# bmowdisk.net
KiCad netlist of a schematic drawn in EAGLE
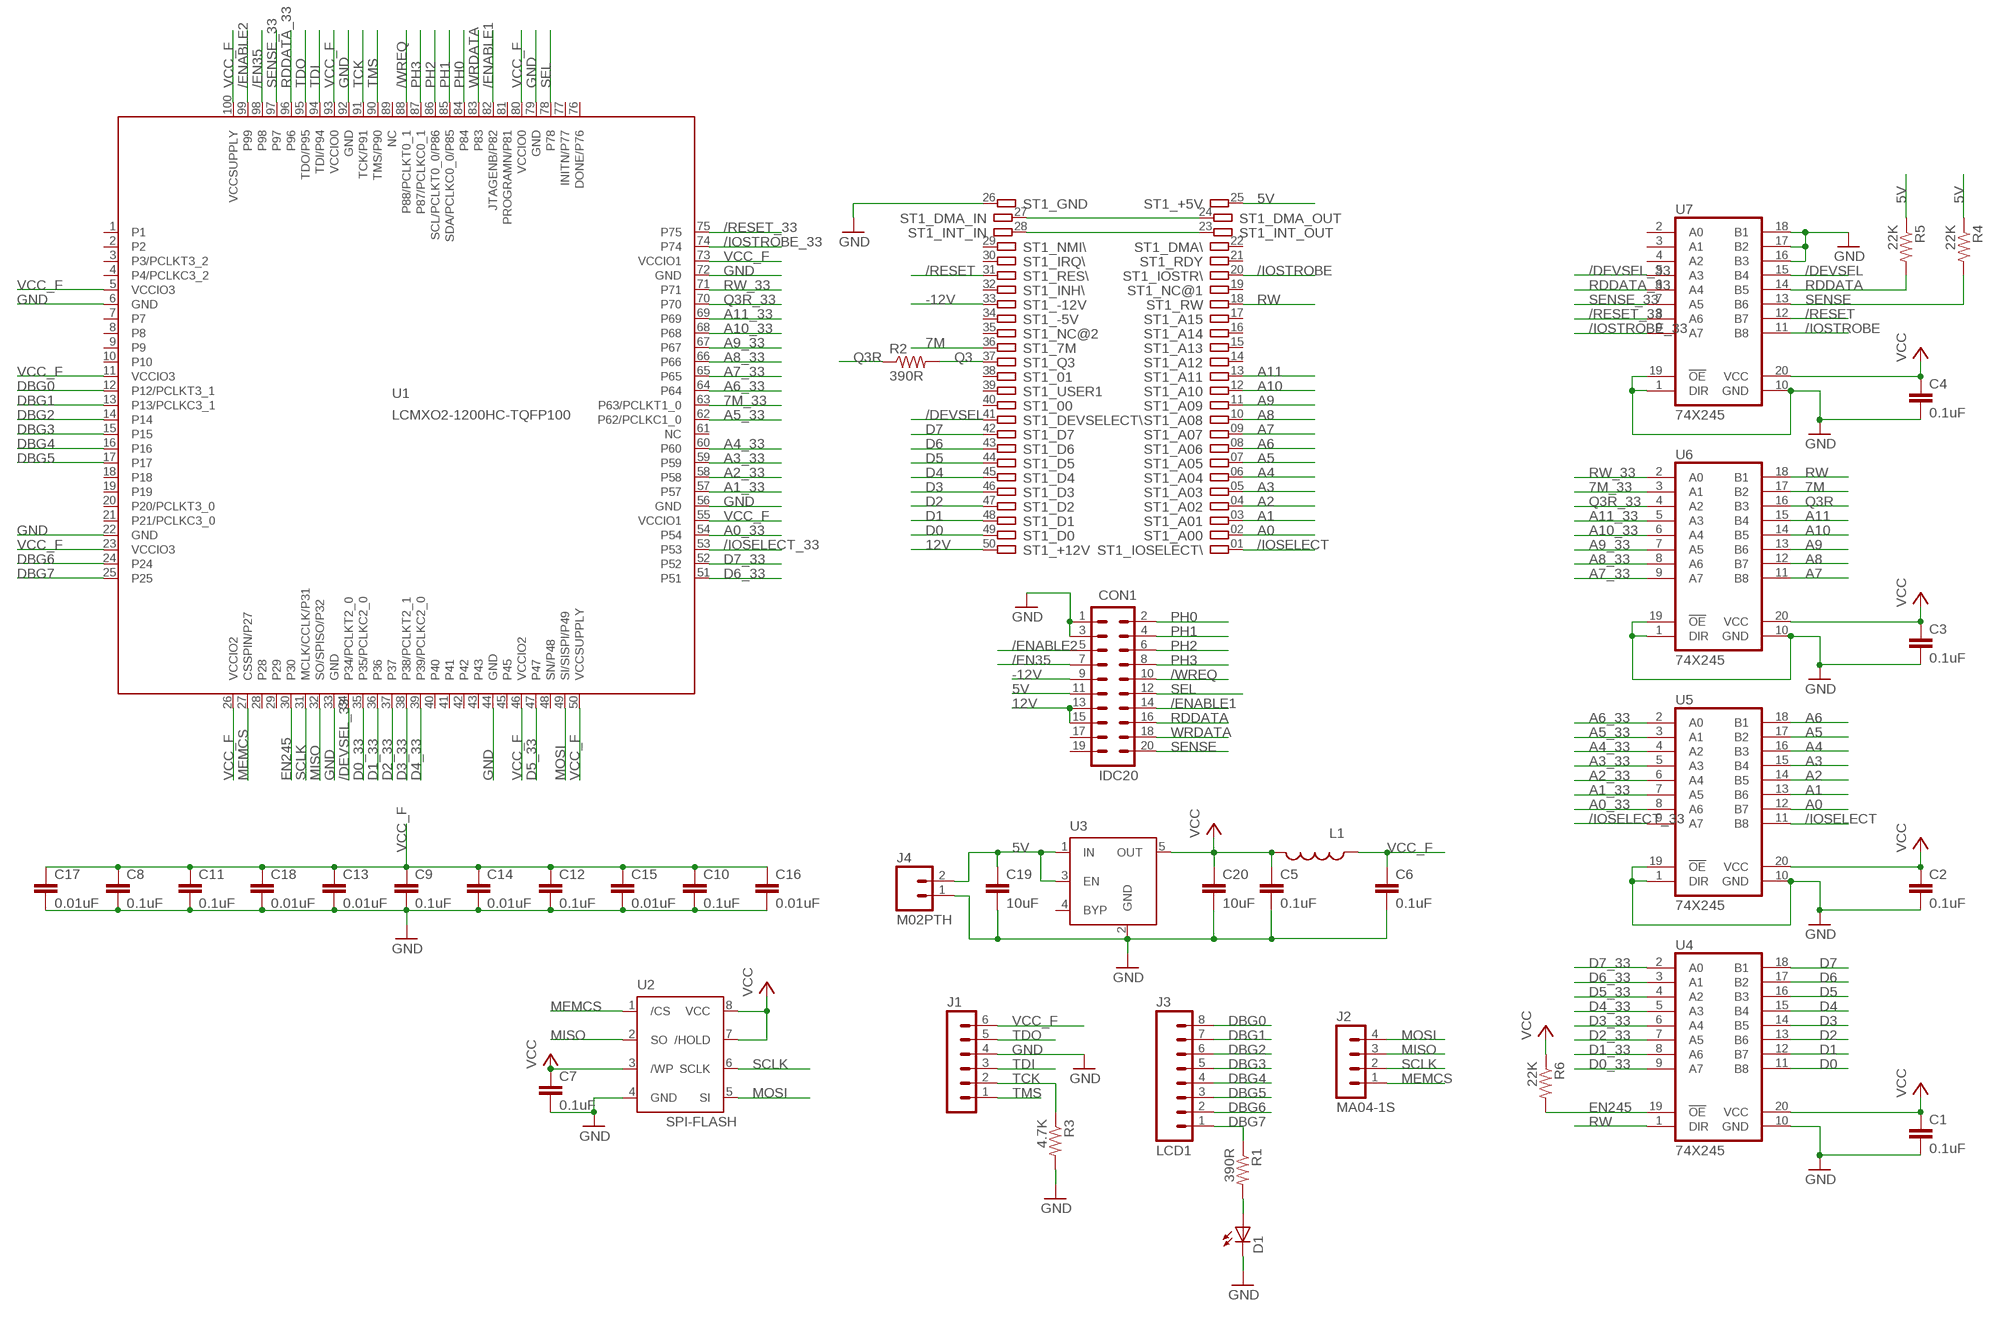
[diagram p0: schematic, sheet 1]

(export (version "E")
  (design (tool "Eeschema 10.0.6"))
  (components
    (comp (ref "C1")
      (value "0.1uF")
      (footprint "eagle-import:0805")
      (libsource (lib "eagle-import") (part "CAP0805"))
    )
    (comp (ref "C2")
      (value "0.1uF")
      (footprint "eagle-import:0805")
      (libsource (lib "eagle-import") (part "CAP0805"))
    )
    (comp (ref "C3")
      (value "0.1uF")
      (footprint "eagle-import:0805")
      (libsource (lib "eagle-import") (part "CAP0805"))
    )
    (comp (ref "C4")
      (value "0.1uF")
      (footprint "eagle-import:0805")
      (libsource (lib "eagle-import") (part "CAP0805"))
    )
    (comp (ref "C5")
      (value "0.1uF")
      (footprint "eagle-import:0805")
      (libsource (lib "eagle-import") (part "CAP0805"))
    )
    (comp (ref "C6")
      (value "0.1uF")
      (footprint "eagle-import:0805")
      (libsource (lib "eagle-import") (part "CAP0805"))
    )
    (comp (ref "C7")
      (value "0.1uF")
      (footprint "eagle-import:0805")
      (libsource (lib "eagle-import") (part "CAP0805"))
    )
    (comp (ref "C8")
      (value "0.1uF")
      (footprint "eagle-import:0805")
      (libsource (lib "eagle-import") (part "CAP0805"))
    )
    (comp (ref "C9")
      (value "0.1uF")
      (footprint "eagle-import:0805")
      (libsource (lib "eagle-import") (part "CAP0805"))
    )
    (comp (ref "C10")
      (value "0.1uF")
      (footprint "eagle-import:0805")
      (libsource (lib "eagle-import") (part "CAP0805"))
    )
    (comp (ref "C11")
      (value "0.1uF")
      (footprint "eagle-import:0805")
      (libsource (lib "eagle-import") (part "CAP0805"))
    )
    (comp (ref "C12")
      (value "0.1uF")
      (footprint "eagle-import:0805")
      (libsource (lib "eagle-import") (part "CAP0805"))
    )
    (comp (ref "C13")
      (value "0.01uF")
      (footprint "eagle-import:0805")
      (libsource (lib "eagle-import") (part "CAP0805"))
    )
    (comp (ref "C14")
      (value "0.01uF")
      (footprint "eagle-import:0805")
      (libsource (lib "eagle-import") (part "CAP0805"))
    )
    (comp (ref "C15")
      (value "0.01uF")
      (footprint "eagle-import:0805")
      (libsource (lib "eagle-import") (part "CAP0805"))
    )
    (comp (ref "C16")
      (value "0.01uF")
      (footprint "eagle-import:0805")
      (libsource (lib "eagle-import") (part "CAP0805"))
    )
    (comp (ref "C17")
      (value "0.01uF")
      (footprint "eagle-import:0805")
      (libsource (lib "eagle-import") (part "CAP0805"))
    )
    (comp (ref "C18")
      (value "0.01uF")
      (footprint "eagle-import:0805")
      (libsource (lib "eagle-import") (part "CAP0805"))
    )
    (comp (ref "C19")
      (value "10uF")
      (footprint "eagle-import:0805")
      (libsource (lib "eagle-import") (part "CAP0805"))
    )
    (comp (ref "C20")
      (value "10uF")
      (footprint "eagle-import:0805")
      (libsource (lib "eagle-import") (part "CAP0805"))
    )
    (comp (ref "CON1")
      (value "IDC20")
      (footprint "eagle-import:IDC20")
      (libsource (lib "eagle-import") (part "IDC20"))
    )
    (comp (ref "D1")
      (value "LEDCHIP-LED0805")
      (footprint "eagle-import:CHIP-LED0805")
      (libsource (lib "eagle-import") (part "LEDCHIP-LED0805"))
    )
    (comp (ref "J1")
      (value "MA06-1NORMAL")
      (footprint "eagle-import:MA06-1")
      (libsource (lib "eagle-import") (part "MA06-1NORMAL"))
    )
    (comp (ref "J2")
      (value "MA04-1S")
      (footprint "eagle-import:MA04-1")
      (libsource (lib "eagle-import") (part "MA04-1S"))
    )
    (comp (ref "J3")
      (value "LCD1")
      (footprint "eagle-import:1X08")
      (libsource (lib "eagle-import") (part "M081X08"))
    )
    (comp (ref "J4")
      (value "M02PTH")
      (footprint "eagle-import:1X02")
      (libsource (lib "eagle-import") (part "M02PTH"))
    )
    (comp (ref "L1")
      (value "INDUCTOR0805")
      (footprint "eagle-import:0805")
      (libsource (lib "eagle-import") (part "INDUCTOR0805"))
    )
    (comp (ref "R1")
      (value "390R")
      (footprint "eagle-import:0805")
      (libsource (lib "eagle-import") (part "RESISTOR0805-RES"))
    )
    (comp (ref "R2")
      (value "390R")
      (footprint "eagle-import:0805")
      (libsource (lib "eagle-import") (part "RESISTOR0805-RES"))
    )
    (comp (ref "R3")
      (value "4.7K")
      (footprint "eagle-import:0805")
      (libsource (lib "eagle-import") (part "RESISTOR0805-RES"))
    )
    (comp (ref "R4")
      (value "22K")
      (footprint "eagle-import:0805")
      (libsource (lib "eagle-import") (part "RESISTOR0805-RES"))
    )
    (comp (ref "R5")
      (value "22K")
      (footprint "eagle-import:0805")
      (libsource (lib "eagle-import") (part "RESISTOR0805-RES"))
    )
    (comp (ref "R6")
      (value "22K")
      (footprint "eagle-import:0805")
      (libsource (lib "eagle-import") (part "RESISTOR0805-RES"))
    )
    (comp (ref "ST1")
      (value "A2-50PINMINI")
      (footprint "eagle-import:A2-50PIN-MINI")
      (libsource (lib "eagle-import") (part "A2-50PINMINI"))
    )
    (comp (ref "U1")
      (value "LCMXO2-1200HC-TQFP100")
      (footprint "eagle-import:TQFP100")
      (libsource (lib "eagle-import") (part "LCMXO2-1200HC-TQFP100"))
    )
    (comp (ref "U2")
      (value "SPI-FLASH")
      (footprint "eagle-import:SOIC08")
      (libsource (lib "eagle-import") (part "SPI-FLASH"))
    )
    (comp (ref "U3")
      (value "MIC5219XX")
      (footprint "eagle-import:SOT23-5")
      (libsource (lib "eagle-import") (part "MIC5219XX"))
    )
    (comp (ref "U4")
      (value "74X245")
      (footprint "eagle-import:SSOP20")
      (libsource (lib "eagle-import") (part "74X245"))
    )
    (comp (ref "U5")
      (value "74X245")
      (footprint "eagle-import:SSOP20")
      (libsource (lib "eagle-import") (part "74X245"))
    )
    (comp (ref "U6")
      (value "74X245")
      (footprint "eagle-import:SSOP20")
      (libsource (lib "eagle-import") (part "74X245"))
    )
    (comp (ref "U7")
      (value "74X245")
      (footprint "eagle-import:SSOP20")
      (libsource (lib "eagle-import") (part "74X245"))
    )
  )
  (nets
    (net (code "1") (name "/-12V") (class "Default")
      (node (ref "CON1") (pin "9") (pinfunction "9_9") (pintype "passive"))
      (node (ref "ST1") (pin "33") (pinfunction "P_33") (pintype "bidirectional"))
    )
    (net (code "2") (name "/5V") (class "Default")
      (node (ref "C19") (pin "1") (pinfunction "1_1") (pintype "passive"))
      (node (ref "CON1") (pin "11") (pinfunction "11_11") (pintype "passive"))
      (node (ref "J4") (pin "2") (pinfunction "2_2") (pintype "passive"))
      (node (ref "R4") (pin "1") (pinfunction "1_1") (pintype "passive"))
      (node (ref "R5") (pin "1") (pinfunction "1_1") (pintype "passive"))
      (node (ref "ST1") (pin "25") (pinfunction "P_25") (pintype "bidirectional"))
      (node (ref "U3") (pin "1") (pinfunction "IN_1") (pintype "input"))
      (node (ref "U3") (pin "3") (pinfunction "EN_3") (pintype "input"))
    )
    (net (code "3") (name "/7M") (class "Default")
      (node (ref "ST1") (pin "36") (pinfunction "P_36") (pintype "bidirectional"))
      (node (ref "U6") (pin "17") (pinfunction "B2_17") (pintype "output"))
    )
    (net (code "4") (name "/7M_33") (class "Default")
      (node (ref "U1") (pin "63") (pinfunction "P63/PCLKT1_0_63") (pintype "bidirectional"))
      (node (ref "U6") (pin "3") (pinfunction "A1_3") (pintype "input"))
    )
    (net (code "5") (name "/12V") (class "Default")
      (node (ref "CON1") (pin "13") (pinfunction "13_13") (pintype "passive"))
      (node (ref "CON1") (pin "15") (pinfunction "15_15") (pintype "passive"))
      (node (ref "ST1") (pin "50") (pinfunction "P_50") (pintype "bidirectional"))
    )
    (net (code "6") (name "/A0") (class "Default")
      (node (ref "ST1") (pin "02") (pinfunction "P_02") (pintype "bidirectional"))
      (node (ref "U5") (pin "12") (pinfunction "B7_12") (pintype "output"))
    )
    (net (code "7") (name "/A0_33") (class "Default")
      (node (ref "U1") (pin "54") (pinfunction "P54_54") (pintype "bidirectional"))
      (node (ref "U5") (pin "8") (pinfunction "A6_8") (pintype "input"))
    )
    (net (code "8") (name "/A1") (class "Default")
      (node (ref "ST1") (pin "03") (pinfunction "P_03") (pintype "bidirectional"))
      (node (ref "U5") (pin "13") (pinfunction "B6_13") (pintype "output"))
    )
    (net (code "9") (name "/A1_33") (class "Default")
      (node (ref "U1") (pin "57") (pinfunction "P57_57") (pintype "bidirectional"))
      (node (ref "U5") (pin "7") (pinfunction "A5_7") (pintype "input"))
    )
    (net (code "10") (name "/A2") (class "Default")
      (node (ref "ST1") (pin "04") (pinfunction "P_04") (pintype "bidirectional"))
      (node (ref "U5") (pin "14") (pinfunction "B5_14") (pintype "output"))
    )
    (net (code "11") (name "/A2_33") (class "Default")
      (node (ref "U1") (pin "58") (pinfunction "P58_58") (pintype "bidirectional"))
      (node (ref "U5") (pin "6") (pinfunction "A4_6") (pintype "input"))
    )
    (net (code "12") (name "/A3") (class "Default")
      (node (ref "ST1") (pin "05") (pinfunction "P_05") (pintype "bidirectional"))
      (node (ref "U5") (pin "15") (pinfunction "B4_15") (pintype "output"))
    )
    (net (code "13") (name "/A3_33") (class "Default")
      (node (ref "U1") (pin "59") (pinfunction "P59_59") (pintype "bidirectional"))
      (node (ref "U5") (pin "5") (pinfunction "A3_5") (pintype "input"))
    )
    (net (code "14") (name "/A4") (class "Default")
      (node (ref "ST1") (pin "06") (pinfunction "P_06") (pintype "bidirectional"))
      (node (ref "U5") (pin "16") (pinfunction "B3_16") (pintype "output"))
    )
    (net (code "15") (name "/A4_33") (class "Default")
      (node (ref "U1") (pin "60") (pinfunction "P60_60") (pintype "bidirectional"))
      (node (ref "U5") (pin "4") (pinfunction "A2_4") (pintype "input"))
    )
    (net (code "16") (name "/A5") (class "Default")
      (node (ref "ST1") (pin "07") (pinfunction "P_07") (pintype "bidirectional"))
      (node (ref "U5") (pin "17") (pinfunction "B2_17") (pintype "output"))
    )
    (net (code "17") (name "/A5_33") (class "Default")
      (node (ref "U1") (pin "62") (pinfunction "P62/PCLKC1_0_62") (pintype "bidirectional"))
      (node (ref "U5") (pin "3") (pinfunction "A1_3") (pintype "input"))
    )
    (net (code "18") (name "/A6") (class "Default")
      (node (ref "ST1") (pin "08") (pinfunction "P_08") (pintype "bidirectional"))
      (node (ref "U5") (pin "18") (pinfunction "B1_18") (pintype "output"))
    )
    (net (code "19") (name "/A6_33") (class "Default")
      (node (ref "U1") (pin "64") (pinfunction "P64_64") (pintype "bidirectional"))
      (node (ref "U5") (pin "2") (pinfunction "A0_2") (pintype "input"))
    )
    (net (code "20") (name "/A7") (class "Default")
      (node (ref "ST1") (pin "09") (pinfunction "P_09") (pintype "bidirectional"))
      (node (ref "U6") (pin "11") (pinfunction "B8_11") (pintype "output"))
    )
    (net (code "21") (name "/A7_33") (class "Default")
      (node (ref "U1") (pin "65") (pinfunction "P65_65") (pintype "bidirectional"))
      (node (ref "U6") (pin "9") (pinfunction "A7_9") (pintype "input"))
    )
    (net (code "22") (name "/A8") (class "Default")
      (node (ref "ST1") (pin "10") (pinfunction "P_10") (pintype "bidirectional"))
      (node (ref "U6") (pin "12") (pinfunction "B7_12") (pintype "output"))
    )
    (net (code "23") (name "/A8_33") (class "Default")
      (node (ref "U1") (pin "66") (pinfunction "P66_66") (pintype "bidirectional"))
      (node (ref "U6") (pin "8") (pinfunction "A6_8") (pintype "input"))
    )
    (net (code "24") (name "/A9") (class "Default")
      (node (ref "ST1") (pin "11") (pinfunction "P_11") (pintype "bidirectional"))
      (node (ref "U6") (pin "13") (pinfunction "B6_13") (pintype "output"))
    )
    (net (code "25") (name "/A9_33") (class "Default")
      (node (ref "U1") (pin "67") (pinfunction "P67_67") (pintype "bidirectional"))
      (node (ref "U6") (pin "7") (pinfunction "A5_7") (pintype "input"))
    )
    (net (code "26") (name "/A10") (class "Default")
      (node (ref "ST1") (pin "12") (pinfunction "P_12") (pintype "bidirectional"))
      (node (ref "U6") (pin "14") (pinfunction "B5_14") (pintype "output"))
    )
    (net (code "27") (name "/A10_33") (class "Default")
      (node (ref "U1") (pin "68") (pinfunction "P68_68") (pintype "bidirectional"))
      (node (ref "U6") (pin "6") (pinfunction "A4_6") (pintype "input"))
    )
    (net (code "28") (name "/A11") (class "Default")
      (node (ref "ST1") (pin "13") (pinfunction "P_13") (pintype "bidirectional"))
      (node (ref "U6") (pin "15") (pinfunction "B4_15") (pintype "output"))
    )
    (net (code "29") (name "/A11_33") (class "Default")
      (node (ref "U1") (pin "69") (pinfunction "P69_69") (pintype "bidirectional"))
      (node (ref "U6") (pin "5") (pinfunction "A3_5") (pintype "input"))
    )
    (net (code "30") (name "/D0") (class "Default")
      (node (ref "ST1") (pin "49") (pinfunction "P_49") (pintype "bidirectional"))
      (node (ref "U4") (pin "11") (pinfunction "B8_11") (pintype "output"))
    )
    (net (code "31") (name "/D0_33") (class "Default")
      (node (ref "U1") (pin "35") (pinfunction "P35/PCLKC2_0_35") (pintype "bidirectional"))
      (node (ref "U4") (pin "9") (pinfunction "A7_9") (pintype "input"))
    )
    (net (code "32") (name "/D1") (class "Default")
      (node (ref "ST1") (pin "48") (pinfunction "P_48") (pintype "bidirectional"))
      (node (ref "U4") (pin "12") (pinfunction "B7_12") (pintype "output"))
    )
    (net (code "33") (name "/D1_33") (class "Default")
      (node (ref "U1") (pin "36") (pinfunction "P36_36") (pintype "bidirectional"))
      (node (ref "U4") (pin "8") (pinfunction "A6_8") (pintype "input"))
    )
    (net (code "34") (name "/D2") (class "Default")
      (node (ref "ST1") (pin "47") (pinfunction "P_47") (pintype "bidirectional"))
      (node (ref "U4") (pin "13") (pinfunction "B6_13") (pintype "output"))
    )
    (net (code "35") (name "/D2_33") (class "Default")
      (node (ref "U1") (pin "37") (pinfunction "P37_37") (pintype "bidirectional"))
      (node (ref "U4") (pin "7") (pinfunction "A5_7") (pintype "input"))
    )
    (net (code "36") (name "/D3") (class "Default")
      (node (ref "ST1") (pin "46") (pinfunction "P_46") (pintype "bidirectional"))
      (node (ref "U4") (pin "14") (pinfunction "B5_14") (pintype "output"))
    )
    (net (code "37") (name "/D3_33") (class "Default")
      (node (ref "U1") (pin "38") (pinfunction "P38/PCLKT2_1_38") (pintype "bidirectional"))
      (node (ref "U4") (pin "6") (pinfunction "A4_6") (pintype "input"))
    )
    (net (code "38") (name "/D4") (class "Default")
      (node (ref "ST1") (pin "45") (pinfunction "P_45") (pintype "bidirectional"))
      (node (ref "U4") (pin "15") (pinfunction "B4_15") (pintype "output"))
    )
    (net (code "39") (name "/D4_33") (class "Default")
      (node (ref "U1") (pin "39") (pinfunction "P39/PCLKC2_0_39") (pintype "bidirectional"))
      (node (ref "U4") (pin "5") (pinfunction "A3_5") (pintype "input"))
    )
    (net (code "40") (name "/D5") (class "Default")
      (node (ref "ST1") (pin "44") (pinfunction "P_44") (pintype "bidirectional"))
      (node (ref "U4") (pin "16") (pinfunction "B3_16") (pintype "output"))
    )
    (net (code "41") (name "/D5_33") (class "Default")
      (node (ref "U1") (pin "47") (pinfunction "P47_47") (pintype "bidirectional"))
      (node (ref "U4") (pin "4") (pinfunction "A2_4") (pintype "input"))
    )
    (net (code "42") (name "/D6") (class "Default")
      (node (ref "ST1") (pin "43") (pinfunction "P_43") (pintype "bidirectional"))
      (node (ref "U4") (pin "17") (pinfunction "B2_17") (pintype "output"))
    )
    (net (code "43") (name "/D6_33") (class "Default")
      (node (ref "U1") (pin "51") (pinfunction "P51_51") (pintype "bidirectional"))
      (node (ref "U4") (pin "3") (pinfunction "A1_3") (pintype "input"))
    )
    (net (code "44") (name "/D7") (class "Default")
      (node (ref "ST1") (pin "42") (pinfunction "P_42") (pintype "bidirectional"))
      (node (ref "U4") (pin "18") (pinfunction "B1_18") (pintype "output"))
    )
    (net (code "45") (name "/D7_33") (class "Default")
      (node (ref "U1") (pin "52") (pinfunction "P52_52") (pintype "bidirectional"))
      (node (ref "U4") (pin "2") (pinfunction "A0_2") (pintype "input"))
    )
    (net (code "46") (name "/DBG0") (class "Default")
      (node (ref "J3") (pin "8") (pinfunction "8_8") (pintype "passive"))
      (node (ref "U1") (pin "12") (pinfunction "P12/PCLKT3_1_12") (pintype "bidirectional"))
    )
    (net (code "47") (name "/DBG1") (class "Default")
      (node (ref "J3") (pin "7") (pinfunction "7_7") (pintype "passive"))
      (node (ref "U1") (pin "13") (pinfunction "P13/PCLKC3_1_13") (pintype "bidirectional"))
    )
    (net (code "48") (name "/DBG2") (class "Default")
      (node (ref "J3") (pin "6") (pinfunction "6_6") (pintype "passive"))
      (node (ref "U1") (pin "14") (pinfunction "P14_14") (pintype "bidirectional"))
    )
    (net (code "49") (name "/DBG3") (class "Default")
      (node (ref "J3") (pin "5") (pinfunction "5_5") (pintype "passive"))
      (node (ref "U1") (pin "15") (pinfunction "P15_15") (pintype "bidirectional"))
    )
    (net (code "50") (name "/DBG4") (class "Default")
      (node (ref "J3") (pin "4") (pinfunction "4_4") (pintype "passive"))
      (node (ref "U1") (pin "16") (pinfunction "P16_16") (pintype "bidirectional"))
    )
    (net (code "51") (name "/DBG5") (class "Default")
      (node (ref "J3") (pin "3") (pinfunction "3_3") (pintype "passive"))
      (node (ref "U1") (pin "17") (pinfunction "P17_17") (pintype "bidirectional"))
    )
    (net (code "52") (name "/DBG6") (class "Default")
      (node (ref "J3") (pin "2") (pinfunction "2_2") (pintype "passive"))
      (node (ref "U1") (pin "24") (pinfunction "P24_24") (pintype "bidirectional"))
    )
    (net (code "53") (name "/DBG7") (class "Default")
      (node (ref "J3") (pin "1") (pinfunction "1_1") (pintype "passive"))
      (node (ref "R1") (pin "1") (pinfunction "1_1") (pintype "passive"))
      (node (ref "U1") (pin "25") (pinfunction "P25_25") (pintype "bidirectional"))
    )
    (net (code "54") (name "/EN245") (class "Default")
      (node (ref "R6") (pin "2") (pinfunction "2_2") (pintype "passive"))
      (node (ref "U1") (pin "30") (pinfunction "P30_30") (pintype "bidirectional"))
      (node (ref "U4") (pin "19") (pinfunction "~{OE}_19") (pintype "input"))
    )
    (net (code "55") (name "/MEMCS") (class "Default")
      (node (ref "J2") (pin "1") (pinfunction "1_1") (pintype "passive"))
      (node (ref "U1") (pin "27") (pinfunction "CSSPIN/P27_27") (pintype "bidirectional"))
      (node (ref "U2") (pin "1") (pinfunction "/CS_1") (pintype "input"))
    )
    (net (code "56") (name "/MISO") (class "Default")
      (node (ref "J2") (pin "3") (pinfunction "3_3") (pintype "passive"))
      (node (ref "U1") (pin "32") (pinfunction "SO/SPISO/P32_32") (pintype "bidirectional"))
      (node (ref "U2") (pin "2") (pinfunction "SO_2") (pintype "input"))
    )
    (net (code "57") (name "/MOSI") (class "Default")
      (node (ref "J2") (pin "4") (pinfunction "4_4") (pintype "passive"))
      (node (ref "U1") (pin "49") (pinfunction "SI/SISPI/P49_49") (pintype "bidirectional"))
      (node (ref "U2") (pin "5") (pinfunction "SI_5") (pintype "output"))
    )
    (net (code "58") (name "/PH0") (class "Default")
      (node (ref "CON1") (pin "2") (pinfunction "2_2") (pintype "passive"))
      (node (ref "U1") (pin "84") (pinfunction "P84_84") (pintype "bidirectional"))
    )
    (net (code "59") (name "/PH1") (class "Default")
      (node (ref "CON1") (pin "4") (pinfunction "4_4") (pintype "passive"))
      (node (ref "U1") (pin "85") (pinfunction "SDA/PCLKC0_0/P85_85") (pintype "bidirectional"))
    )
    (net (code "60") (name "/PH2") (class "Default")
      (node (ref "CON1") (pin "6") (pinfunction "6_6") (pintype "passive"))
      (node (ref "U1") (pin "86") (pinfunction "SCL/PCLKT0_0/P86_86") (pintype "bidirectional"))
    )
    (net (code "61") (name "/PH3") (class "Default")
      (node (ref "CON1") (pin "8") (pinfunction "8_8") (pintype "passive"))
      (node (ref "U1") (pin "87") (pinfunction "P87/PCLKC0_1_87") (pintype "bidirectional"))
    )
    (net (code "62") (name "/Q3") (class "Default")
      (node (ref "R2") (pin "2") (pinfunction "2_2") (pintype "passive"))
      (node (ref "ST1") (pin "37") (pinfunction "P_37") (pintype "bidirectional"))
    )
    (net (code "63") (name "/Q3R") (class "Default")
      (node (ref "R2") (pin "1") (pinfunction "1_1") (pintype "passive"))
      (node (ref "U6") (pin "16") (pinfunction "B3_16") (pintype "output"))
    )
    (net (code "64") (name "/Q3R_33") (class "Default")
      (node (ref "U1") (pin "70") (pinfunction "P70_70") (pintype "bidirectional"))
      (node (ref "U6") (pin "4") (pinfunction "A2_4") (pintype "input"))
    )
    (net (code "65") (name "/RDDATA") (class "Default")
      (node (ref "CON1") (pin "16") (pinfunction "16_16") (pintype "passive"))
      (node (ref "R5") (pin "2") (pinfunction "2_2") (pintype "passive"))
      (node (ref "U7") (pin "14") (pinfunction "B5_14") (pintype "output"))
    )
    (net (code "66") (name "/RDDATA_33") (class "Default")
      (node (ref "U1") (pin "96") (pinfunction "P96_96") (pintype "bidirectional"))
      (node (ref "U7") (pin "6") (pinfunction "A4_6") (pintype "input"))
    )
    (net (code "67") (name "/RW") (class "Default")
      (node (ref "ST1") (pin "18") (pinfunction "P_18") (pintype "bidirectional"))
      (node (ref "U4") (pin "1") (pinfunction "DIR_1") (pintype "input"))
      (node (ref "U6") (pin "18") (pinfunction "B1_18") (pintype "output"))
    )
    (net (code "68") (name "/RW_33") (class "Default")
      (node (ref "U1") (pin "71") (pinfunction "P71_71") (pintype "bidirectional"))
      (node (ref "U6") (pin "2") (pinfunction "A0_2") (pintype "input"))
    )
    (net (code "69") (name "/SCLK") (class "Default")
      (node (ref "J2") (pin "2") (pinfunction "2_2") (pintype "passive"))
      (node (ref "U1") (pin "31") (pinfunction "MCLK/CCLK/P31_31") (pintype "bidirectional"))
      (node (ref "U2") (pin "6") (pinfunction "SCLK_6") (pintype "output"))
    )
    (net (code "70") (name "/SEL") (class "Default")
      (node (ref "CON1") (pin "12") (pinfunction "12_12") (pintype "passive"))
      (node (ref "U1") (pin "78") (pinfunction "P78_78") (pintype "bidirectional"))
    )
    (net (code "71") (name "/SENSE") (class "Default")
      (node (ref "CON1") (pin "20") (pinfunction "20_20") (pintype "passive"))
      (node (ref "R4") (pin "2") (pinfunction "2_2") (pintype "passive"))
      (node (ref "U7") (pin "13") (pinfunction "B6_13") (pintype "output"))
    )
    (net (code "72") (name "/SENSE_33") (class "Default")
      (node (ref "U1") (pin "97") (pinfunction "P97_97") (pintype "bidirectional"))
      (node (ref "U7") (pin "7") (pinfunction "A5_7") (pintype "input"))
    )
    (net (code "73") (name "/TCK") (class "Default")
      (node (ref "J1") (pin "2") (pinfunction "2_2") (pintype "passive"))
      (node (ref "R3") (pin "1") (pinfunction "1_1") (pintype "passive"))
      (node (ref "U1") (pin "91") (pinfunction "TCK/P91_91") (pintype "bidirectional"))
    )
    (net (code "74") (name "/TDI") (class "Default")
      (node (ref "J1") (pin "3") (pinfunction "3_3") (pintype "passive"))
      (node (ref "U1") (pin "94") (pinfunction "TDI/P94_94") (pintype "bidirectional"))
    )
    (net (code "75") (name "/TDO") (class "Default")
      (node (ref "J1") (pin "5") (pinfunction "5_5") (pintype "passive"))
      (node (ref "U1") (pin "95") (pinfunction "TDO/P95_95") (pintype "bidirectional"))
    )
    (net (code "76") (name "/TMS") (class "Default")
      (node (ref "J1") (pin "1") (pinfunction "1_1") (pintype "passive"))
      (node (ref "U1") (pin "90") (pinfunction "TMS/P90_90") (pintype "bidirectional"))
    )
    (net (code "77") (name "/VCC_F") (class "Default")
      (node (ref "C10") (pin "1") (pinfunction "1_1") (pintype "passive"))
      (node (ref "C11") (pin "1") (pinfunction "1_1") (pintype "passive"))
      (node (ref "C12") (pin "1") (pinfunction "1_1") (pintype "passive"))
      (node (ref "C13") (pin "1") (pinfunction "1_1") (pintype "passive"))
      (node (ref "C14") (pin "1") (pinfunction "1_1") (pintype "passive"))
      (node (ref "C15") (pin "1") (pinfunction "1_1") (pintype "passive"))
      (node (ref "C16") (pin "1") (pinfunction "1_1") (pintype "passive"))
      (node (ref "C17") (pin "1") (pinfunction "1_1") (pintype "passive"))
      (node (ref "C18") (pin "1") (pinfunction "1_1") (pintype "passive"))
      (node (ref "C6") (pin "1") (pinfunction "1_1") (pintype "passive"))
      (node (ref "C8") (pin "1") (pinfunction "1_1") (pintype "passive"))
      (node (ref "C9") (pin "1") (pinfunction "1_1") (pintype "passive"))
      (node (ref "J1") (pin "6") (pinfunction "6_6") (pintype "passive"))
      (node (ref "L1") (pin "1") (pinfunction "1_1") (pintype "passive"))
      (node (ref "U1") (pin "100") (pinfunction "VCCSUPPLY_100") (pintype "power_in"))
      (node (ref "U1") (pin "11") (pinfunction "VCCIO3_11") (pintype "power_in"))
      (node (ref "U1") (pin "23") (pinfunction "VCCIO3_23") (pintype "power_in"))
      (node (ref "U1") (pin "26") (pinfunction "VCCIO2_26") (pintype "power_in"))
      (node (ref "U1") (pin "46") (pinfunction "VCCIO2_46") (pintype "power_in"))
      (node (ref "U1") (pin "5") (pinfunction "VCCIO3_5") (pintype "power_in"))
      (node (ref "U1") (pin "50") (pinfunction "VCCSUPPLY_50") (pintype "power_in"))
      (node (ref "U1") (pin "55") (pinfunction "VCCIO1_55") (pintype "power_in"))
      (node (ref "U1") (pin "73") (pinfunction "VCCIO1_73") (pintype "power_in"))
      (node (ref "U1") (pin "80") (pinfunction "VCCIO0_80") (pintype "power_in"))
      (node (ref "U1") (pin "93") (pinfunction "VCCIO0_93") (pintype "power_in"))
    )
    (net (code "78") (name "/WRDATA") (class "Default")
      (node (ref "CON1") (pin "18") (pinfunction "18_18") (pintype "passive"))
      (node (ref "U1") (pin "83") (pinfunction "P83_83") (pintype "bidirectional"))
    )
    (net (code "79") (name "/{slash}DEVSEL") (class "Default")
      (node (ref "ST1") (pin "41") (pinfunction "P_41") (pintype "bidirectional"))
      (node (ref "U7") (pin "15") (pinfunction "B4_15") (pintype "output"))
    )
    (net (code "80") (name "/{slash}DEVSEL_33") (class "Default")
      (node (ref "U1") (pin "34") (pinfunction "P34/PCLKT2_0_34") (pintype "bidirectional"))
      (node (ref "U7") (pin "5") (pinfunction "A3_5") (pintype "input"))
    )
    (net (code "81") (name "/{slash}EN35") (class "Default")
      (node (ref "CON1") (pin "7") (pinfunction "7_7") (pintype "passive"))
      (node (ref "U1") (pin "98") (pinfunction "P98_98") (pintype "bidirectional"))
    )
    (net (code "82") (name "/{slash}ENABLE1") (class "Default")
      (node (ref "CON1") (pin "14") (pinfunction "14_14") (pintype "passive"))
      (node (ref "U1") (pin "82") (pinfunction "JTAGENB/P82_82") (pintype "bidirectional"))
    )
    (net (code "83") (name "/{slash}ENABLE2") (class "Default")
      (node (ref "CON1") (pin "5") (pinfunction "5_5") (pintype "passive"))
      (node (ref "U1") (pin "99") (pinfunction "P99_99") (pintype "bidirectional"))
    )
    (net (code "84") (name "/{slash}IOSELECT") (class "Default")
      (node (ref "ST1") (pin "01") (pinfunction "P_01") (pintype "bidirectional"))
      (node (ref "U5") (pin "11") (pinfunction "B8_11") (pintype "output"))
    )
    (net (code "85") (name "/{slash}IOSELECT_33") (class "Default")
      (node (ref "U1") (pin "53") (pinfunction "P53_53") (pintype "bidirectional"))
      (node (ref "U5") (pin "9") (pinfunction "A7_9") (pintype "input"))
    )
    (net (code "86") (name "/{slash}IOSTROBE") (class "Default")
      (node (ref "ST1") (pin "20") (pinfunction "P_20") (pintype "bidirectional"))
      (node (ref "U7") (pin "11") (pinfunction "B8_11") (pintype "output"))
    )
    (net (code "87") (name "/{slash}IOSTROBE_33") (class "Default")
      (node (ref "U1") (pin "74") (pinfunction "P74_74") (pintype "bidirectional"))
      (node (ref "U7") (pin "9") (pinfunction "A7_9") (pintype "input"))
    )
    (net (code "88") (name "/{slash}RESET") (class "Default")
      (node (ref "ST1") (pin "31") (pinfunction "P_31") (pintype "bidirectional"))
      (node (ref "U7") (pin "12") (pinfunction "B7_12") (pintype "output"))
    )
    (net (code "89") (name "/{slash}RESET_33") (class "Default")
      (node (ref "U1") (pin "75") (pinfunction "P75_75") (pintype "bidirectional"))
      (node (ref "U7") (pin "8") (pinfunction "A6_8") (pintype "input"))
    )
    (net (code "90") (name "/{slash}WREQ") (class "Default")
      (node (ref "CON1") (pin "10") (pinfunction "10_10") (pintype "passive"))
      (node (ref "U1") (pin "88") (pinfunction "P88/PCLKT0_1_88") (pintype "bidirectional"))
    )
    (net (code "91") (name "GND") (class "Default")
      (node (ref "C1") (pin "2") (pinfunction "2_2") (pintype "passive"))
      (node (ref "C10") (pin "2") (pinfunction "2_2") (pintype "passive"))
      (node (ref "C11") (pin "2") (pinfunction "2_2") (pintype "passive"))
      (node (ref "C12") (pin "2") (pinfunction "2_2") (pintype "passive"))
      (node (ref "C13") (pin "2") (pinfunction "2_2") (pintype "passive"))
      (node (ref "C14") (pin "2") (pinfunction "2_2") (pintype "passive"))
      (node (ref "C15") (pin "2") (pinfunction "2_2") (pintype "passive"))
      (node (ref "C16") (pin "2") (pinfunction "2_2") (pintype "passive"))
      (node (ref "C17") (pin "2") (pinfunction "2_2") (pintype "passive"))
      (node (ref "C18") (pin "2") (pinfunction "2_2") (pintype "passive"))
      (node (ref "C19") (pin "2") (pinfunction "2_2") (pintype "passive"))
      (node (ref "C2") (pin "2") (pinfunction "2_2") (pintype "passive"))
      (node (ref "C20") (pin "2") (pinfunction "2_2") (pintype "passive"))
      (node (ref "C3") (pin "2") (pinfunction "2_2") (pintype "passive"))
      (node (ref "C4") (pin "2") (pinfunction "2_2") (pintype "passive"))
      (node (ref "C5") (pin "2") (pinfunction "2_2") (pintype "passive"))
      (node (ref "C6") (pin "2") (pinfunction "2_2") (pintype "passive"))
      (node (ref "C7") (pin "2") (pinfunction "2_2") (pintype "passive"))
      (node (ref "C8") (pin "2") (pinfunction "2_2") (pintype "passive"))
      (node (ref "C9") (pin "2") (pinfunction "2_2") (pintype "passive"))
      (node (ref "CON1") (pin "1") (pinfunction "1_1") (pintype "passive"))
      (node (ref "CON1") (pin "3") (pinfunction "3_3") (pintype "passive"))
      (node (ref "D1") (pin "C") (pinfunction "C_C") (pintype "passive"))
      (node (ref "J1") (pin "4") (pinfunction "4_4") (pintype "passive"))
      (node (ref "J4") (pin "1") (pinfunction "1_1") (pintype "passive"))
      (node (ref "R3") (pin "2") (pinfunction "2_2") (pintype "passive"))
      (node (ref "ST1") (pin "26") (pinfunction "P_26") (pintype "bidirectional"))
      (node (ref "U1") (pin "22") (pinfunction "GND_22") (pintype "power_in"))
      (node (ref "U1") (pin "33") (pinfunction "GND_33") (pintype "power_in"))
      (node (ref "U1") (pin "44") (pinfunction "GND_44") (pintype "power_in"))
      (node (ref "U1") (pin "56") (pinfunction "GND_56") (pintype "power_in"))
      (node (ref "U1") (pin "6") (pinfunction "GND_6") (pintype "power_in"))
      (node (ref "U1") (pin "72") (pinfunction "GND_72") (pintype "power_in"))
      (node (ref "U1") (pin "79") (pinfunction "GND_79") (pintype "power_in"))
      (node (ref "U1") (pin "92") (pinfunction "GND_92") (pintype "power_in"))
      (node (ref "U2") (pin "4") (pinfunction "GND_4") (pintype "power_in"))
      (node (ref "U3") (pin "2") (pinfunction "GND_2") (pintype "power_in"))
      (node (ref "U4") (pin "10") (pinfunction "GND_10") (pintype "power_in"))
      (node (ref "U5") (pin "1") (pinfunction "DIR_1") (pintype "input"))
      (node (ref "U5") (pin "10") (pinfunction "GND_10") (pintype "power_in"))
      (node (ref "U5") (pin "19") (pinfunction "~{OE}_19") (pintype "input"))
      (node (ref "U6") (pin "1") (pinfunction "DIR_1") (pintype "input"))
      (node (ref "U6") (pin "10") (pinfunction "GND_10") (pintype "power_in"))
      (node (ref "U6") (pin "19") (pinfunction "~{OE}_19") (pintype "input"))
      (node (ref "U7") (pin "1") (pinfunction "DIR_1") (pintype "input"))
      (node (ref "U7") (pin "10") (pinfunction "GND_10") (pintype "power_in"))
      (node (ref "U7") (pin "16") (pinfunction "B3_16") (pintype "output"))
      (node (ref "U7") (pin "17") (pinfunction "B2_17") (pintype "output"))
      (node (ref "U7") (pin "18") (pinfunction "B1_18") (pintype "output"))
      (node (ref "U7") (pin "19") (pinfunction "~{OE}_19") (pintype "input"))
    )
    (net (code "92") (name "Net-(D1-PadA)") (class "Default")
      (node (ref "D1") (pin "A") (pinfunction "A_A") (pintype "passive"))
      (node (ref "R1") (pin "2") (pinfunction "2_2") (pintype "passive"))
    )
    (net (code "93") (name "Net-(ST1AH-P)") (class "Default")
      (node (ref "ST1") (pin "24") (pinfunction "P_24") (pintype "bidirectional"))
      (node (ref "ST1") (pin "27") (pinfunction "P_27") (pintype "bidirectional"))
    )
    (net (code "94") (name "Net-(ST1AL-P)") (class "Default")
      (node (ref "ST1") (pin "23") (pinfunction "P_23") (pintype "bidirectional"))
      (node (ref "ST1") (pin "28") (pinfunction "P_28") (pintype "bidirectional"))
    )
    (net (code "95") (name "VCC") (class "Default")
      (node (ref "C1") (pin "1") (pinfunction "1_1") (pintype "passive"))
      (node (ref "C2") (pin "1") (pinfunction "1_1") (pintype "passive"))
      (node (ref "C20") (pin "1") (pinfunction "1_1") (pintype "passive"))
      (node (ref "C3") (pin "1") (pinfunction "1_1") (pintype "passive"))
      (node (ref "C4") (pin "1") (pinfunction "1_1") (pintype "passive"))
      (node (ref "C5") (pin "1") (pinfunction "1_1") (pintype "passive"))
      (node (ref "C7") (pin "1") (pinfunction "1_1") (pintype "passive"))
      (node (ref "L1") (pin "2") (pinfunction "2_2") (pintype "passive"))
      (node (ref "R6") (pin "1") (pinfunction "1_1") (pintype "passive"))
      (node (ref "U2") (pin "3") (pinfunction "/WP_3") (pintype "passive"))
      (node (ref "U2") (pin "7") (pinfunction "/HOLD_7") (pintype "output"))
      (node (ref "U2") (pin "8") (pinfunction "VCC_8") (pintype "power_in"))
      (node (ref "U3") (pin "5") (pinfunction "OUT_5") (pintype "output"))
      (node (ref "U4") (pin "20") (pinfunction "VCC_20") (pintype "power_in"))
      (node (ref "U5") (pin "20") (pinfunction "VCC_20") (pintype "power_in"))
      (node (ref "U6") (pin "20") (pinfunction "VCC_20") (pintype "power_in"))
      (node (ref "U7") (pin "20") (pinfunction "VCC_20") (pintype "power_in"))
    )
    (net (code "96") (name "unconnected-(CON1-Pad17)") (class "Default")
      (node (ref "CON1") (pin "17") (pinfunction "17_17") (pintype "passive"))
    )
    (net (code "97") (name "unconnected-(CON1-Pad19)") (class "Default")
      (node (ref "CON1") (pin "19") (pinfunction "19_19") (pintype "passive"))
    )
    (net (code "98") (name "unconnected-(ST1AG-P-Pad22)") (class "Default")
      (node (ref "ST1") (pin "22") (pinfunction "P_22") (pintype "bidirectional"))
    )
    (net (code "99") (name "unconnected-(ST1AK-P-Pad32)") (class "Default")
      (node (ref "ST1") (pin "32") (pinfunction "P_32") (pintype "bidirectional"))
    )
    (net (code "100") (name "unconnected-(ST1AP-P-Pad30)") (class "Default")
      (node (ref "ST1") (pin "30") (pinfunction "P_30") (pintype "bidirectional"))
    )
    (net (code "101") (name "unconnected-(ST1AQ-P-Pad19)") (class "Default")
      (node (ref "ST1") (pin "19") (pinfunction "P_19") (pintype "bidirectional"))
    )
    (net (code "102") (name "unconnected-(ST1AR-P-Pad35)") (class "Default")
      (node (ref "ST1") (pin "35") (pinfunction "P_35") (pintype "bidirectional"))
    )
    (net (code "103") (name "unconnected-(ST1AS-P-Pad29)") (class "Default")
      (node (ref "ST1") (pin "29") (pinfunction "P_29") (pintype "bidirectional"))
    )
    (net (code "104") (name "unconnected-(ST1AU-P-Pad21)") (class "Default")
      (node (ref "ST1") (pin "21") (pinfunction "P_21") (pintype "bidirectional"))
    )
    (net (code "105") (name "unconnected-(ST1AX-P-Pad39)") (class "Default")
      (node (ref "ST1") (pin "39") (pinfunction "P_39") (pintype "bidirectional"))
    )
    (net (code "106") (name "unconnected-(ST1D-P-Pad34)") (class "Default")
      (node (ref "ST1") (pin "34") (pinfunction "P_34") (pintype "bidirectional"))
    )
    (net (code "107") (name "unconnected-(ST1E-P-Pad40)") (class "Default")
      (node (ref "ST1") (pin "40") (pinfunction "P_40") (pintype "bidirectional"))
    )
    (net (code "108") (name "unconnected-(ST1F-P-Pad38)") (class "Default")
      (node (ref "ST1") (pin "38") (pinfunction "P_38") (pintype "bidirectional"))
    )
    (net (code "109") (name "unconnected-(ST1T-P-Pad14)") (class "Default")
      (node (ref "ST1") (pin "14") (pinfunction "P_14") (pintype "bidirectional"))
    )
    (net (code "110") (name "unconnected-(ST1U-P-Pad15)") (class "Default")
      (node (ref "ST1") (pin "15") (pinfunction "P_15") (pintype "bidirectional"))
    )
    (net (code "111") (name "unconnected-(ST1V-P-Pad16)") (class "Default")
      (node (ref "ST1") (pin "16") (pinfunction "P_16") (pintype "bidirectional"))
    )
    (net (code "112") (name "unconnected-(ST1W-P-Pad17)") (class "Default")
      (node (ref "ST1") (pin "17") (pinfunction "P_17") (pintype "bidirectional"))
    )
    (net (code "113") (name "unconnected-(U1-DONE{slash}P76-Pad76)") (class "Default")
      (node (ref "U1") (pin "76") (pinfunction "DONE/P76_76") (pintype "bidirectional"))
    )
    (net (code "114") (name "unconnected-(U1-INITN{slash}P77-Pad77)") (class "Default")
      (node (ref "U1") (pin "77") (pinfunction "INITN/P77_77") (pintype "bidirectional"))
    )
    (net (code "115") (name "unconnected-(U1-NC-Pad61)") (class "Default")
      (node (ref "U1") (pin "61") (pinfunction "NC_61") (pintype "no_connect"))
    )
    (net (code "116") (name "unconnected-(U1-NC-Pad89)") (class "Default")
      (node (ref "U1") (pin "89") (pinfunction "NC_89") (pintype "no_connect"))
    )
    (net (code "117") (name "unconnected-(U1-P1-Pad1)") (class "Default")
      (node (ref "U1") (pin "1") (pinfunction "P1_1") (pintype "bidirectional"))
    )
    (net (code "118") (name "unconnected-(U1-P2-Pad2)") (class "Default")
      (node (ref "U1") (pin "2") (pinfunction "P2_2") (pintype "bidirectional"))
    )
    (net (code "119") (name "unconnected-(U1-P3{slash}PCLKT3_2-Pad3)") (class "Default")
      (node (ref "U1") (pin "3") (pinfunction "P3/PCLKT3_2_3") (pintype "bidirectional"))
    )
    (net (code "120") (name "unconnected-(U1-P4{slash}PCLKC3_2-Pad4)") (class "Default")
      (node (ref "U1") (pin "4") (pinfunction "P4/PCLKC3_2_4") (pintype "bidirectional"))
    )
    (net (code "121") (name "unconnected-(U1-P7-Pad7)") (class "Default")
      (node (ref "U1") (pin "7") (pinfunction "P7_7") (pintype "bidirectional"))
    )
    (net (code "122") (name "unconnected-(U1-P8-Pad8)") (class "Default")
      (node (ref "U1") (pin "8") (pinfunction "P8_8") (pintype "bidirectional"))
    )
    (net (code "123") (name "unconnected-(U1-P9-Pad9)") (class "Default")
      (node (ref "U1") (pin "9") (pinfunction "P9_9") (pintype "bidirectional"))
    )
    (net (code "124") (name "unconnected-(U1-P10-Pad10)") (class "Default")
      (node (ref "U1") (pin "10") (pinfunction "P10_10") (pintype "bidirectional"))
    )
    (net (code "125") (name "unconnected-(U1-P18-Pad18)") (class "Default")
      (node (ref "U1") (pin "18") (pinfunction "P18_18") (pintype "bidirectional"))
    )
    (net (code "126") (name "unconnected-(U1-P19-Pad19)") (class "Default")
      (node (ref "U1") (pin "19") (pinfunction "P19_19") (pintype "bidirectional"))
    )
    (net (code "127") (name "unconnected-(U1-P20{slash}PCLKT3_0-Pad20)") (class "Default")
      (node (ref "U1") (pin "20") (pinfunction "P20/PCLKT3_0_20") (pintype "bidirectional"))
    )
    (net (code "128") (name "unconnected-(U1-P21{slash}PCLKC3_0-Pad21)") (class "Default")
      (node (ref "U1") (pin "21") (pinfunction "P21/PCLKC3_0_21") (pintype "bidirectional"))
    )
    (net (code "129") (name "unconnected-(U1-P28-Pad28)") (class "Default")
      (node (ref "U1") (pin "28") (pinfunction "P28_28") (pintype "bidirectional"))
    )
    (net (code "130") (name "unconnected-(U1-P29-Pad29)") (class "Default")
      (node (ref "U1") (pin "29") (pinfunction "P29_29") (pintype "bidirectional"))
    )
    (net (code "131") (name "unconnected-(U1-P40-Pad40)") (class "Default")
      (node (ref "U1") (pin "40") (pinfunction "P40_40") (pintype "bidirectional"))
    )
    (net (code "132") (name "unconnected-(U1-P41-Pad41)") (class "Default")
      (node (ref "U1") (pin "41") (pinfunction "P41_41") (pintype "bidirectional"))
    )
    (net (code "133") (name "unconnected-(U1-P42-Pad42)") (class "Default")
      (node (ref "U1") (pin "42") (pinfunction "P42_42") (pintype "bidirectional"))
    )
    (net (code "134") (name "unconnected-(U1-P43-Pad43)") (class "Default")
      (node (ref "U1") (pin "43") (pinfunction "P43_43") (pintype "bidirectional"))
    )
    (net (code "135") (name "unconnected-(U1-P45-Pad45)") (class "Default")
      (node (ref "U1") (pin "45") (pinfunction "P45_45") (pintype "bidirectional"))
    )
    (net (code "136") (name "unconnected-(U1-PROGRAMN{slash}P81-Pad81)") (class "Default")
      (node (ref "U1") (pin "81") (pinfunction "PROGRAMN/P81_81") (pintype "bidirectional"))
    )
    (net (code "137") (name "unconnected-(U1-SN{slash}P48-Pad48)") (class "Default")
      (node (ref "U1") (pin "48") (pinfunction "SN/P48_48") (pintype "bidirectional"))
    )
    (net (code "138") (name "unconnected-(U3-BYP-Pad4)") (class "Default")
      (node (ref "U3") (pin "4") (pinfunction "BYP_4") (pintype "passive"))
    )
    (net (code "139") (name "unconnected-(U7-A0-Pad2)") (class "Default")
      (node (ref "U7") (pin "2") (pinfunction "A0_2") (pintype "input"))
    )
    (net (code "140") (name "unconnected-(U7-A1-Pad3)") (class "Default")
      (node (ref "U7") (pin "3") (pinfunction "A1_3") (pintype "input"))
    )
    (net (code "141") (name "unconnected-(U7-A2-Pad4)") (class "Default")
      (node (ref "U7") (pin "4") (pinfunction "A2_4") (pintype "input"))
    )
  )
)
